# Power_PCB.net
KiCad netlist of a schematic drawn in EAGLE
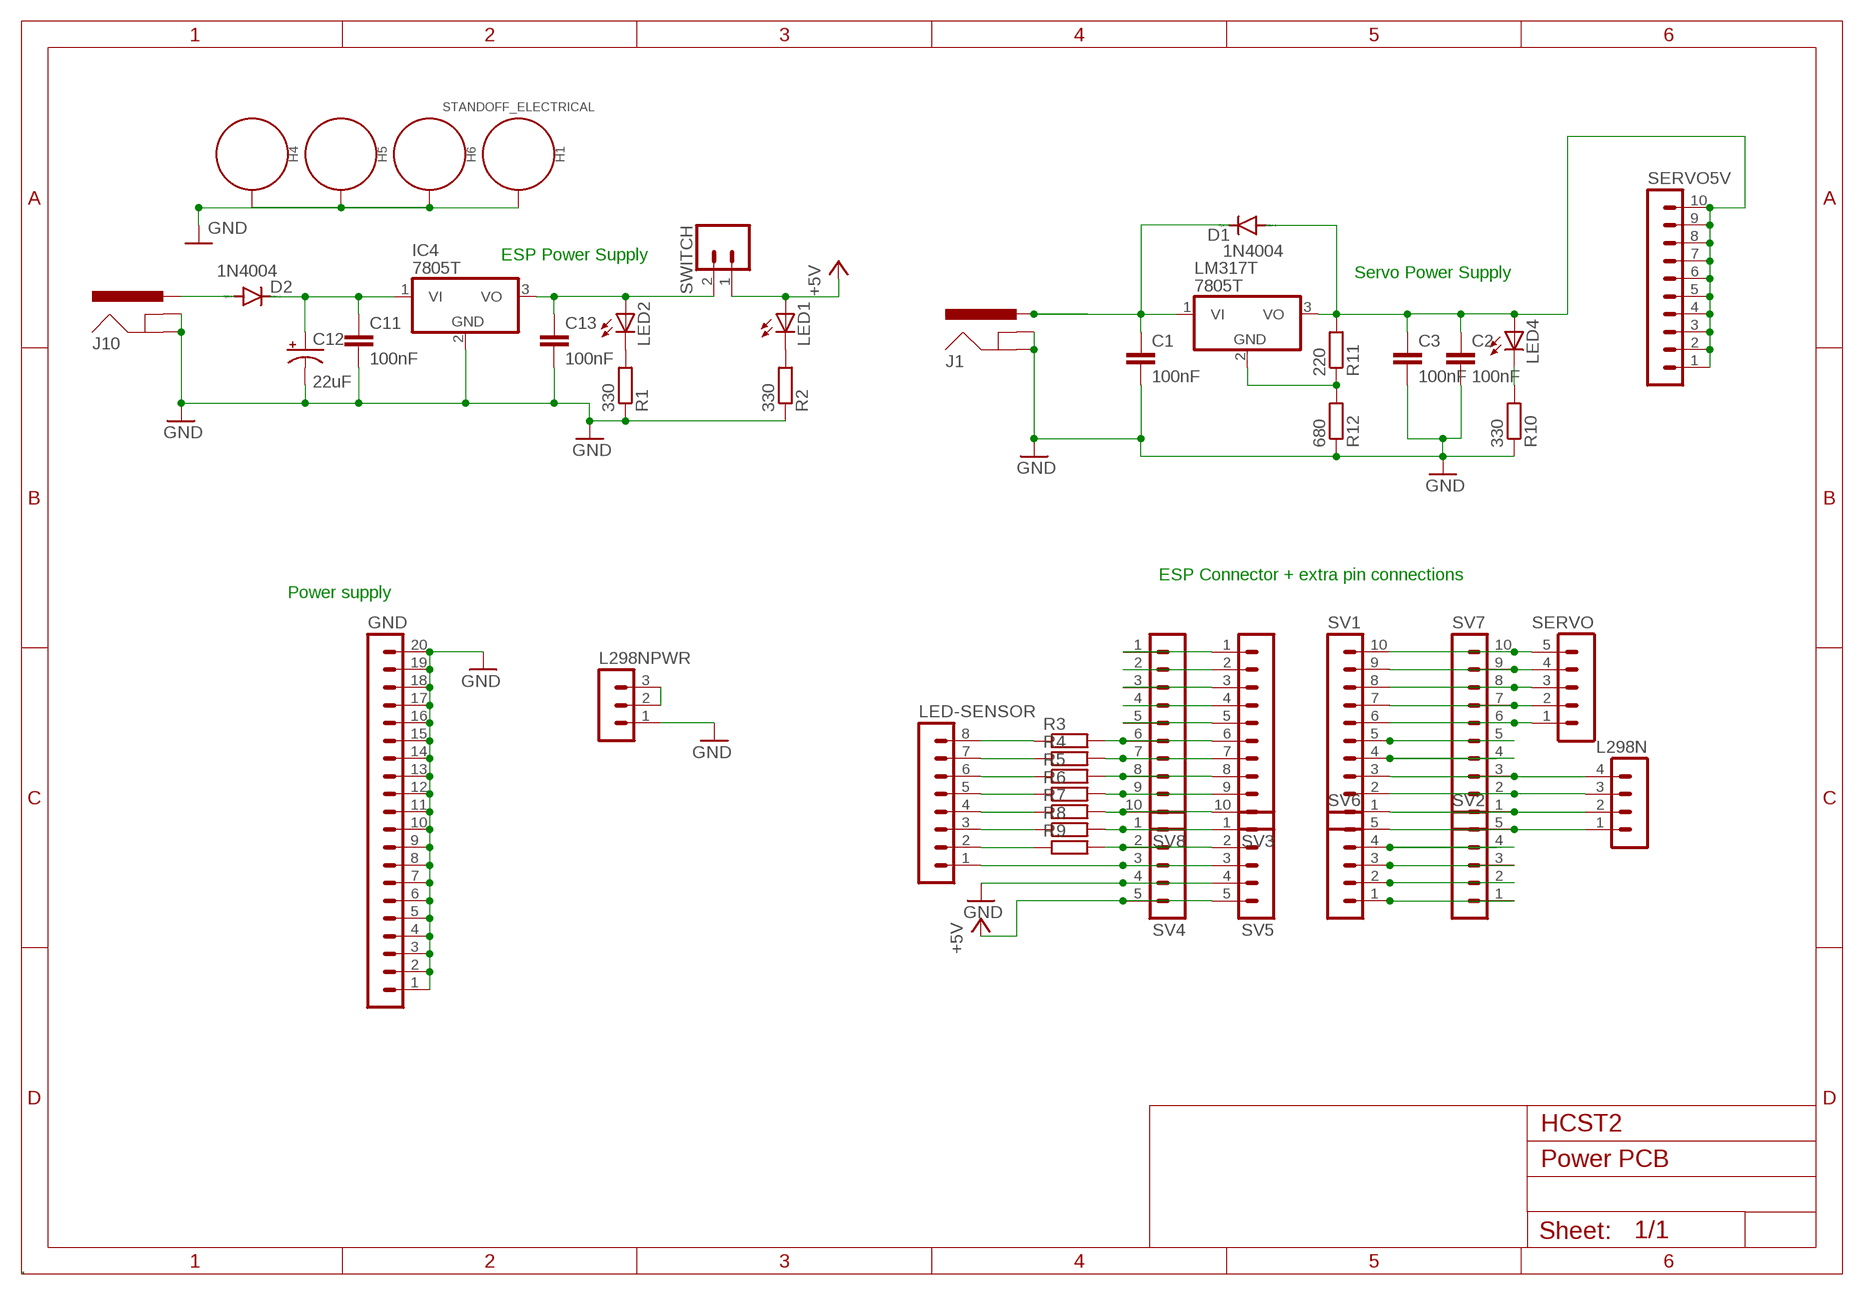
[diagram p0: schematic, sheet 1]

(export (version "E")
  (design (tool "Eeschema 10.0.6"))
  (components
    (comp (ref "C1")
      (value "100nF")
      (footprint "eagle-import:C2.5-2")
      (libsource (lib "eagle-import") (part "C2.5/2"))
    )
    (comp (ref "C2")
      (value "100nF")
      (footprint "eagle-import:C2.5-2")
      (libsource (lib "eagle-import") (part "C2.5/2"))
    )
    (comp (ref "C3")
      (value "100nF")
      (footprint "eagle-import:C2.5-2")
      (libsource (lib "eagle-import") (part "C2.5/2"))
    )
    (comp (ref "C11")
      (value "100nF")
      (footprint "eagle-import:C2.5-2")
      (libsource (lib "eagle-import") (part "C2.5/2"))
    )
    (comp (ref "C12")
      (value "22uF")
      (footprint "eagle-import:E2,5-7")
      (libsource (lib "eagle-import") (part "CPOL-USE2.5-7"))
    )
    (comp (ref "C13")
      (value "100nF")
      (footprint "eagle-import:C2.5-2")
      (libsource (lib "eagle-import") (part "C2.5/2"))
    )
    (comp (ref "D1")
      (value "1N4004")
      (footprint "eagle-import:DO41-10")
      (libsource (lib "eagle-import") (part "1N4004"))
    )
    (comp (ref "D2")
      (value "1N4004")
      (footprint "eagle-import:DO41-10")
      (libsource (lib "eagle-import") (part "1N4004"))
    )
    (comp (ref "GND")
      (value "MA20-1")
      (footprint "eagle-import:MA20-1")
      (libsource (lib "eagle-import") (part "MA20-1"))
    )
    (comp (ref "H1")
      (value "STANDOFF_ELECTRICAL")
      (footprint "eagle-import:STANDOFF-ELECTRICAL")
      (libsource (lib "eagle-import") (part "STANDOFF_ELECTRICAL"))
    )
    (comp (ref "H4")
      (value "STANDOFF_ELECTRICAL")
      (footprint "eagle-import:STANDOFF-ELECTRICAL")
      (libsource (lib "eagle-import") (part "SparkFun-Hardware_519_STANDOFF_ELECTRICAL"))
    )
    (comp (ref "H5")
      (value "STANDOFF_ELECTRICAL")
      (footprint "eagle-import:STANDOFF-ELECTRICAL")
      (libsource (lib "eagle-import") (part "SparkFun-Hardware_519_STANDOFF_ELECTRICAL"))
    )
    (comp (ref "H6")
      (value "STANDOFF_ELECTRICAL")
      (footprint "eagle-import:STANDOFF-ELECTRICAL")
      (libsource (lib "eagle-import") (part "SparkFun-Hardware_519_STANDOFF_ELECTRICAL"))
    )
    (comp (ref "IC4")
      (value "7805T")
      (footprint "eagle-import:TO220H")
      (libsource (lib "eagle-import") (part "78T05"))
    )
    (comp (ref "J1")
      (value "EL311-ROBOT_SPARKFUN-CONNECTORS_POWER_JACKPTH")
      (footprint "eagle-import:EL311-ROBOT_SPARKFUN-CONNECTORS_POWER_JACK_PTH")
      (libsource (lib "eagle-import") (part "EL311-ROBOT_SPARKFUN-CONNECTORS_POWER_JACKPTH"))
    )
    (comp (ref "J10")
      (value "EL311-ROBOT_SPARKFUN-CONNECTORS_POWER_JACKPTH")
      (footprint "eagle-import:EL311-ROBOT_SPARKFUN-CONNECTORS_POWER_JACK_PTH")
      (libsource (lib "eagle-import") (part "EL311-ROBOT_SPARKFUN-CONNECTORS_POWER_JACKPTH"))
    )
    (comp (ref "L298N")
      (value "MA04-1")
      (footprint "eagle-import:MA04-1")
      (libsource (lib "eagle-import") (part "MA04-1"))
    )
    (comp (ref "L298NPWR")
      (value "MA03-1")
      (footprint "eagle-import:MA03-1")
      (libsource (lib "eagle-import") (part "MA03-1"))
    )
    (comp (ref "LED-SENSOR")
      (value "MA08-1")
      (footprint "eagle-import:MA08-1")
      (libsource (lib "eagle-import") (part "MA08-1"))
    )
    (comp (ref "LED1")
      (value "LED3MM")
      (footprint "eagle-import:LED3MM")
      (libsource (lib "eagle-import") (part "LED3MM"))
    )
    (comp (ref "LED2")
      (value "LED3MM")
      (footprint "eagle-import:LED3MM")
      (libsource (lib "eagle-import") (part "LED3MM"))
    )
    (comp (ref "LED4")
      (value "LED3MM")
      (footprint "eagle-import:LED3MM")
      (libsource (lib "eagle-import") (part "LED3MM"))
    )
    (comp (ref "LM317T")
      (value "7805T")
      (footprint "eagle-import:TO220H")
      (libsource (lib "eagle-import") (part "78T05"))
    )
    (comp (ref "R1")
      (value "330")
      (footprint "eagle-import:0207_10")
      (libsource (lib "eagle-import") (part "R-EU_0207/10"))
    )
    (comp (ref "R2")
      (value "330")
      (footprint "eagle-import:0207_10")
      (libsource (lib "eagle-import") (part "R-EU_0207/10"))
    )
    (comp (ref "R3")
      (value "R-EU_0207/10")
      (footprint "eagle-import:0207_10")
      (libsource (lib "eagle-import") (part "R-EU_0207/10"))
    )
    (comp (ref "R4")
      (value "R-EU_0207/10")
      (footprint "eagle-import:0207_10")
      (libsource (lib "eagle-import") (part "R-EU_0207/10"))
    )
    (comp (ref "R5")
      (value "R-EU_0207/10")
      (footprint "eagle-import:0207_10")
      (libsource (lib "eagle-import") (part "R-EU_0207/10"))
    )
    (comp (ref "R6")
      (value "R-EU_0207/10")
      (footprint "eagle-import:0207_10")
      (libsource (lib "eagle-import") (part "R-EU_0207/10"))
    )
    (comp (ref "R7")
      (value "R-EU_0207/10")
      (footprint "eagle-import:0207_10")
      (libsource (lib "eagle-import") (part "R-EU_0207/10"))
    )
    (comp (ref "R8")
      (value "R-EU_0207/10")
      (footprint "eagle-import:0207_10")
      (libsource (lib "eagle-import") (part "R-EU_0207/10"))
    )
    (comp (ref "R9")
      (value "R-EU_0207/10")
      (footprint "eagle-import:0207_10")
      (libsource (lib "eagle-import") (part "R-EU_0207/10"))
    )
    (comp (ref "R10")
      (value "330")
      (footprint "eagle-import:0207_10")
      (libsource (lib "eagle-import") (part "R-EU_0207/10"))
    )
    (comp (ref "R11")
      (value "220")
      (footprint "eagle-import:0207_10")
      (libsource (lib "eagle-import") (part "R-EU_0207/10"))
    )
    (comp (ref "R12")
      (value "680")
      (footprint "eagle-import:0207_10")
      (libsource (lib "eagle-import") (part "R-EU_0207/10"))
    )
    (comp (ref "SERVO")
      (value "MA05-1")
      (footprint "eagle-import:MA05-1")
      (libsource (lib "eagle-import") (part "MA05-1"))
    )
    (comp (ref "SERVO5V")
      (value "MA10-1")
      (footprint "eagle-import:MA10-1")
      (libsource (lib "eagle-import") (part "MA10-1"))
    )
    (comp (ref "SV1")
      (value "MA10-1")
      (footprint "eagle-import:MA10-1")
      (libsource (lib "eagle-import") (part "MA10-1"))
    )
    (comp (ref "SV2")
      (value "MA05-1")
      (footprint "eagle-import:MA05-1")
      (libsource (lib "eagle-import") (part "MA05-1"))
    )
    (comp (ref "SV3")
      (value "MA10-1")
      (footprint "eagle-import:MA10-1")
      (libsource (lib "eagle-import") (part "MA10-1"))
    )
    (comp (ref "SV4")
      (value "MA05-1")
      (footprint "eagle-import:MA05-1")
      (libsource (lib "eagle-import") (part "MA05-1"))
    )
    (comp (ref "SV5")
      (value "MA05-1")
      (footprint "eagle-import:MA05-1")
      (libsource (lib "eagle-import") (part "MA05-1"))
    )
    (comp (ref "SV6")
      (value "MA05-1")
      (footprint "eagle-import:MA05-1")
      (libsource (lib "eagle-import") (part "MA05-1"))
    )
    (comp (ref "SV7")
      (value "MA10-1")
      (footprint "eagle-import:MA10-1")
      (libsource (lib "eagle-import") (part "MA10-1"))
    )
    (comp (ref "SV8")
      (value "MA10-1")
      (footprint "eagle-import:MA10-1")
      (libsource (lib "eagle-import") (part "MA10-1"))
    )
    (comp (ref "SWITCH")
      (value "CONN_02")
      (footprint "eagle-import:1X02")
      (libsource (lib "eagle-import") (part "CONN_02"))
    )
  )
  (nets
    (net (code "1") (name "+5V") (class "Default")
      (node (ref "LED1") (pin "A") (pinfunction "A_A") (pintype "passive"))
      (node (ref "SV4") (pin "5") (pinfunction "5_5") (pintype "passive"))
      (node (ref "SV5") (pin "5") (pinfunction "5_5") (pintype "passive"))
      (node (ref "SWITCH") (pin "1") (pinfunction "1_1") (pintype "passive"))
    )
    (net (code "2") (name "GND") (class "Default")
      (node (ref "C1") (pin "2") (pinfunction "2_2") (pintype "passive"))
      (node (ref "C11") (pin "2") (pinfunction "2_2") (pintype "passive"))
      (node (ref "C12") (pin "-") (pinfunction "-_-") (pintype "passive"))
      (node (ref "C13") (pin "2") (pinfunction "2_2") (pintype "passive"))
      (node (ref "C2") (pin "2") (pinfunction "2_2") (pintype "passive"))
      (node (ref "C3") (pin "2") (pinfunction "2_2") (pintype "passive"))
      (node (ref "GND") (pin "1") (pinfunction "1_1") (pintype "passive"))
      (node (ref "GND") (pin "10") (pinfunction "10_10") (pintype "passive"))
      (node (ref "GND") (pin "11") (pinfunction "11_11") (pintype "passive"))
      (node (ref "GND") (pin "12") (pinfunction "12_12") (pintype "passive"))
      (node (ref "GND") (pin "13") (pinfunction "13_13") (pintype "passive"))
      (node (ref "GND") (pin "14") (pinfunction "14_14") (pintype "passive"))
      (node (ref "GND") (pin "15") (pinfunction "15_15") (pintype "passive"))
      (node (ref "GND") (pin "16") (pinfunction "16_16") (pintype "passive"))
      (node (ref "GND") (pin "17") (pinfunction "17_17") (pintype "passive"))
      (node (ref "GND") (pin "18") (pinfunction "18_18") (pintype "passive"))
      (node (ref "GND") (pin "19") (pinfunction "19_19") (pintype "passive"))
      (node (ref "GND") (pin "2") (pinfunction "2_2") (pintype "passive"))
      (node (ref "GND") (pin "20") (pinfunction "20_20") (pintype "passive"))
      (node (ref "GND") (pin "3") (pinfunction "3_3") (pintype "passive"))
      (node (ref "GND") (pin "4") (pinfunction "4_4") (pintype "passive"))
      (node (ref "GND") (pin "5") (pinfunction "5_5") (pintype "passive"))
      (node (ref "GND") (pin "6") (pinfunction "6_6") (pintype "passive"))
      (node (ref "GND") (pin "7") (pinfunction "7_7") (pintype "passive"))
      (node (ref "GND") (pin "8") (pinfunction "8_8") (pintype "passive"))
      (node (ref "GND") (pin "9") (pinfunction "9_9") (pintype "passive"))
      (node (ref "H1") (pin "P1") (pinfunction "P$1_P1") (pintype "bidirectional"))
      (node (ref "H4") (pin "P1") (pinfunction "P$1_P1") (pintype "bidirectional"))
      (node (ref "H5") (pin "P1") (pinfunction "P$1_P1") (pintype "bidirectional"))
      (node (ref "H6") (pin "P1") (pinfunction "P$1_P1") (pintype "bidirectional"))
      (node (ref "IC4") (pin "2") (pinfunction "GND_2") (pintype "passive"))
      (node (ref "J1") (pin "GND") (pinfunction "GND_GND") (pintype "bidirectional"))
      (node (ref "J1") (pin "GNDBREAK") (pinfunction "GNDBREAK_GNDBREAK") (pintype "bidirectional"))
      (node (ref "J10") (pin "GND") (pinfunction "GND_GND") (pintype "bidirectional"))
      (node (ref "J10") (pin "GNDBREAK") (pinfunction "GNDBREAK_GNDBREAK") (pintype "bidirectional"))
      (node (ref "L298NPWR") (pin "1") (pinfunction "1_1") (pintype "passive"))
      (node (ref "R1") (pin "1") (pinfunction "1_1") (pintype "passive"))
      (node (ref "R10") (pin "1") (pinfunction "1_1") (pintype "passive"))
      (node (ref "R12") (pin "1") (pinfunction "1_1") (pintype "passive"))
      (node (ref "R2") (pin "1") (pinfunction "1_1") (pintype "passive"))
      (node (ref "SV4") (pin "4") (pinfunction "4_4") (pintype "passive"))
      (node (ref "SV5") (pin "4") (pinfunction "4_4") (pintype "passive"))
    )
    (net (code "3") (name "Net-(D2-PadA)") (class "Default")
      (node (ref "D2") (pin "A") (pinfunction "A_A") (pintype "passive"))
      (node (ref "J10") (pin "PWR") (pinfunction "PWR_PWR") (pintype "bidirectional"))
    )
    (net (code "4") (name "Net-(IC4-VI)") (class "Default")
      (node (ref "C11") (pin "1") (pinfunction "1_1") (pintype "passive"))
      (node (ref "C12") (pin "+") (pinfunction "+_+") (pintype "passive"))
      (node (ref "D2") (pin "C") (pinfunction "C_C") (pintype "passive"))
      (node (ref "IC4") (pin "1") (pinfunction "VI_1") (pintype "input"))
    )
    (net (code "5") (name "Net-(IC4-VO)") (class "Default")
      (node (ref "C13") (pin "1") (pinfunction "1_1") (pintype "passive"))
      (node (ref "IC4") (pin "3") (pinfunction "VO_3") (pintype "passive"))
      (node (ref "LED2") (pin "A") (pinfunction "A_A") (pintype "passive"))
      (node (ref "SWITCH") (pin "2") (pinfunction "2_2") (pintype "passive"))
    )
    (net (code "6") (name "Net-(L298N-Pad1)") (class "Default")
      (node (ref "L298N") (pin "1") (pinfunction "1_1") (pintype "passive"))
      (node (ref "SV2") (pin "5") (pinfunction "5_5") (pintype "passive"))
      (node (ref "SV6") (pin "5") (pinfunction "5_5") (pintype "passive"))
    )
    (net (code "7") (name "Net-(L298N-Pad2)") (class "Default")
      (node (ref "L298N") (pin "2") (pinfunction "2_2") (pintype "passive"))
      (node (ref "SV1") (pin "1") (pinfunction "1_1") (pintype "passive"))
      (node (ref "SV7") (pin "1") (pinfunction "1_1") (pintype "passive"))
    )
    (net (code "8") (name "Net-(L298N-Pad3)") (class "Default")
      (node (ref "L298N") (pin "3") (pinfunction "3_3") (pintype "passive"))
      (node (ref "SV1") (pin "2") (pinfunction "2_2") (pintype "passive"))
      (node (ref "SV7") (pin "2") (pinfunction "2_2") (pintype "passive"))
    )
    (net (code "9") (name "Net-(L298N-Pad4)") (class "Default")
      (node (ref "L298N") (pin "4") (pinfunction "4_4") (pintype "passive"))
      (node (ref "SV1") (pin "3") (pinfunction "3_3") (pintype "passive"))
      (node (ref "SV7") (pin "3") (pinfunction "3_3") (pintype "passive"))
    )
    (net (code "10") (name "Net-(L298NPWR-Pad2)") (class "Default")
      (node (ref "L298NPWR") (pin "2") (pinfunction "2_2") (pintype "passive"))
      (node (ref "L298NPWR") (pin "3") (pinfunction "3_3") (pintype "passive"))
    )
    (net (code "11") (name "Net-(LED-SENSOR-Pad1)") (class "Default")
      (node (ref "LED-SENSOR") (pin "1") (pinfunction "1_1") (pintype "passive"))
      (node (ref "SV4") (pin "3") (pinfunction "3_3") (pintype "passive"))
      (node (ref "SV5") (pin "3") (pinfunction "3_3") (pintype "passive"))
    )
    (net (code "12") (name "Net-(LED-SENSOR-Pad2)") (class "Default")
      (node (ref "LED-SENSOR") (pin "2") (pinfunction "2_2") (pintype "passive"))
      (node (ref "R9") (pin "1") (pinfunction "1_1") (pintype "passive"))
    )
    (net (code "13") (name "Net-(LED-SENSOR-Pad3)") (class "Default")
      (node (ref "LED-SENSOR") (pin "3") (pinfunction "3_3") (pintype "passive"))
      (node (ref "R8") (pin "1") (pinfunction "1_1") (pintype "passive"))
    )
    (net (code "14") (name "Net-(LED-SENSOR-Pad4)") (class "Default")
      (node (ref "LED-SENSOR") (pin "4") (pinfunction "4_4") (pintype "passive"))
      (node (ref "R7") (pin "1") (pinfunction "1_1") (pintype "passive"))
    )
    (net (code "15") (name "Net-(LED-SENSOR-Pad5)") (class "Default")
      (node (ref "LED-SENSOR") (pin "5") (pinfunction "5_5") (pintype "passive"))
      (node (ref "R6") (pin "1") (pinfunction "1_1") (pintype "passive"))
    )
    (net (code "16") (name "Net-(LED-SENSOR-Pad6)") (class "Default")
      (node (ref "LED-SENSOR") (pin "6") (pinfunction "6_6") (pintype "passive"))
      (node (ref "R5") (pin "1") (pinfunction "1_1") (pintype "passive"))
    )
    (net (code "17") (name "Net-(LED-SENSOR-Pad7)") (class "Default")
      (node (ref "LED-SENSOR") (pin "7") (pinfunction "7_7") (pintype "passive"))
      (node (ref "R4") (pin "1") (pinfunction "1_1") (pintype "passive"))
    )
    (net (code "18") (name "Net-(LED-SENSOR-Pad8)") (class "Default")
      (node (ref "LED-SENSOR") (pin "8") (pinfunction "8_8") (pintype "passive"))
      (node (ref "R3") (pin "1") (pinfunction "1_1") (pintype "passive"))
    )
    (net (code "19") (name "Net-(LED1-C)") (class "Default")
      (node (ref "LED1") (pin "K") (pinfunction "C_K") (pintype "passive"))
      (node (ref "R2") (pin "2") (pinfunction "2_2") (pintype "passive"))
    )
    (net (code "20") (name "Net-(LED2-C)") (class "Default")
      (node (ref "LED2") (pin "K") (pinfunction "C_K") (pintype "passive"))
      (node (ref "R1") (pin "2") (pinfunction "2_2") (pintype "passive"))
    )
    (net (code "21") (name "Net-(LED4-C)") (class "Default")
      (node (ref "LED4") (pin "K") (pinfunction "C_K") (pintype "passive"))
      (node (ref "R10") (pin "2") (pinfunction "2_2") (pintype "passive"))
    )
    (net (code "22") (name "Net-(LM317T-GND)") (class "Default")
      (node (ref "LM317T") (pin "2") (pinfunction "GND_2") (pintype "passive"))
      (node (ref "R11") (pin "1") (pinfunction "1_1") (pintype "passive"))
      (node (ref "R12") (pin "2") (pinfunction "2_2") (pintype "passive"))
    )
    (net (code "23") (name "Net-(LM317T-VI)") (class "Default")
      (node (ref "C1") (pin "1") (pinfunction "1_1") (pintype "passive"))
      (node (ref "D1") (pin "C") (pinfunction "C_C") (pintype "passive"))
      (node (ref "J1") (pin "PWR") (pinfunction "PWR_PWR") (pintype "bidirectional"))
      (node (ref "LM317T") (pin "1") (pinfunction "VI_1") (pintype "input"))
    )
    (net (code "24") (name "Net-(LM317T-VO)") (class "Default")
      (node (ref "C2") (pin "1") (pinfunction "1_1") (pintype "passive"))
      (node (ref "C3") (pin "1") (pinfunction "1_1") (pintype "passive"))
      (node (ref "D1") (pin "A") (pinfunction "A_A") (pintype "passive"))
      (node (ref "LED4") (pin "A") (pinfunction "A_A") (pintype "passive"))
      (node (ref "LM317T") (pin "3") (pinfunction "VO_3") (pintype "passive"))
      (node (ref "R11") (pin "2") (pinfunction "2_2") (pintype "passive"))
      (node (ref "SERVO5V") (pin "1") (pinfunction "1_1") (pintype "passive"))
      (node (ref "SERVO5V") (pin "10") (pinfunction "10_10") (pintype "passive"))
      (node (ref "SERVO5V") (pin "2") (pinfunction "2_2") (pintype "passive"))
      (node (ref "SERVO5V") (pin "3") (pinfunction "3_3") (pintype "passive"))
      (node (ref "SERVO5V") (pin "4") (pinfunction "4_4") (pintype "passive"))
      (node (ref "SERVO5V") (pin "5") (pinfunction "5_5") (pintype "passive"))
      (node (ref "SERVO5V") (pin "6") (pinfunction "6_6") (pintype "passive"))
      (node (ref "SERVO5V") (pin "7") (pinfunction "7_7") (pintype "passive"))
      (node (ref "SERVO5V") (pin "8") (pinfunction "8_8") (pintype "passive"))
      (node (ref "SERVO5V") (pin "9") (pinfunction "9_9") (pintype "passive"))
    )
    (net (code "25") (name "Net-(R3-Pad2)") (class "Default")
      (node (ref "R3") (pin "2") (pinfunction "2_2") (pintype "passive"))
      (node (ref "SV3") (pin "6") (pinfunction "6_6") (pintype "passive"))
      (node (ref "SV8") (pin "6") (pinfunction "6_6") (pintype "passive"))
    )
    (net (code "26") (name "Net-(R4-Pad2)") (class "Default")
      (node (ref "R4") (pin "2") (pinfunction "2_2") (pintype "passive"))
      (node (ref "SV3") (pin "7") (pinfunction "7_7") (pintype "passive"))
      (node (ref "SV8") (pin "7") (pinfunction "7_7") (pintype "passive"))
    )
    (net (code "27") (name "Net-(R5-Pad2)") (class "Default")
      (node (ref "R5") (pin "2") (pinfunction "2_2") (pintype "passive"))
      (node (ref "SV3") (pin "8") (pinfunction "8_8") (pintype "passive"))
      (node (ref "SV8") (pin "8") (pinfunction "8_8") (pintype "passive"))
    )
    (net (code "28") (name "Net-(R6-Pad2)") (class "Default")
      (node (ref "R6") (pin "2") (pinfunction "2_2") (pintype "passive"))
      (node (ref "SV3") (pin "9") (pinfunction "9_9") (pintype "passive"))
      (node (ref "SV8") (pin "9") (pinfunction "9_9") (pintype "passive"))
    )
    (net (code "29") (name "Net-(R7-Pad2)") (class "Default")
      (node (ref "R7") (pin "2") (pinfunction "2_2") (pintype "passive"))
      (node (ref "SV3") (pin "10") (pinfunction "10_10") (pintype "passive"))
      (node (ref "SV8") (pin "10") (pinfunction "10_10") (pintype "passive"))
    )
    (net (code "30") (name "Net-(R8-Pad2)") (class "Default")
      (node (ref "R8") (pin "2") (pinfunction "2_2") (pintype "passive"))
      (node (ref "SV4") (pin "1") (pinfunction "1_1") (pintype "passive"))
      (node (ref "SV5") (pin "1") (pinfunction "1_1") (pintype "passive"))
    )
    (net (code "31") (name "Net-(R9-Pad2)") (class "Default")
      (node (ref "R9") (pin "2") (pinfunction "2_2") (pintype "passive"))
      (node (ref "SV4") (pin "2") (pinfunction "2_2") (pintype "passive"))
      (node (ref "SV5") (pin "2") (pinfunction "2_2") (pintype "passive"))
    )
    (net (code "32") (name "Net-(SERVO-Pad1)") (class "Default")
      (node (ref "SERVO") (pin "1") (pinfunction "1_1") (pintype "passive"))
      (node (ref "SV1") (pin "6") (pinfunction "6_6") (pintype "passive"))
      (node (ref "SV7") (pin "6") (pinfunction "6_6") (pintype "passive"))
    )
    (net (code "33") (name "Net-(SERVO-Pad2)") (class "Default")
      (node (ref "SERVO") (pin "2") (pinfunction "2_2") (pintype "passive"))
      (node (ref "SV1") (pin "7") (pinfunction "7_7") (pintype "passive"))
      (node (ref "SV7") (pin "7") (pinfunction "7_7") (pintype "passive"))
    )
    (net (code "34") (name "Net-(SERVO-Pad3)") (class "Default")
      (node (ref "SERVO") (pin "3") (pinfunction "3_3") (pintype "passive"))
      (node (ref "SV1") (pin "8") (pinfunction "8_8") (pintype "passive"))
      (node (ref "SV7") (pin "8") (pinfunction "8_8") (pintype "passive"))
    )
    (net (code "35") (name "Net-(SERVO-Pad4)") (class "Default")
      (node (ref "SERVO") (pin "4") (pinfunction "4_4") (pintype "passive"))
      (node (ref "SV1") (pin "9") (pinfunction "9_9") (pintype "passive"))
      (node (ref "SV7") (pin "9") (pinfunction "9_9") (pintype "passive"))
    )
    (net (code "36") (name "Net-(SERVO-Pad5)") (class "Default")
      (node (ref "SERVO") (pin "5") (pinfunction "5_5") (pintype "passive"))
      (node (ref "SV1") (pin "10") (pinfunction "10_10") (pintype "passive"))
      (node (ref "SV7") (pin "10") (pinfunction "10_10") (pintype "passive"))
    )
    (net (code "37") (name "Net-(SV1-Pad4)") (class "Default")
      (node (ref "SV1") (pin "4") (pinfunction "4_4") (pintype "passive"))
      (node (ref "SV7") (pin "4") (pinfunction "4_4") (pintype "passive"))
    )
    (net (code "38") (name "Net-(SV1-Pad5)") (class "Default")
      (node (ref "SV1") (pin "5") (pinfunction "5_5") (pintype "passive"))
      (node (ref "SV7") (pin "5") (pinfunction "5_5") (pintype "passive"))
    )
    (net (code "39") (name "Net-(SV2-Pad1)") (class "Default")
      (node (ref "SV2") (pin "1") (pinfunction "1_1") (pintype "passive"))
      (node (ref "SV6") (pin "1") (pinfunction "1_1") (pintype "passive"))
    )
    (net (code "40") (name "Net-(SV2-Pad2)") (class "Default")
      (node (ref "SV2") (pin "2") (pinfunction "2_2") (pintype "passive"))
      (node (ref "SV6") (pin "2") (pinfunction "2_2") (pintype "passive"))
    )
    (net (code "41") (name "Net-(SV2-Pad3)") (class "Default")
      (node (ref "SV2") (pin "3") (pinfunction "3_3") (pintype "passive"))
      (node (ref "SV6") (pin "3") (pinfunction "3_3") (pintype "passive"))
    )
    (net (code "42") (name "Net-(SV2-Pad4)") (class "Default")
      (node (ref "SV2") (pin "4") (pinfunction "4_4") (pintype "passive"))
      (node (ref "SV6") (pin "4") (pinfunction "4_4") (pintype "passive"))
    )
    (net (code "43") (name "Net-(SV3-Pad1)") (class "Default")
      (node (ref "SV3") (pin "1") (pinfunction "1_1") (pintype "passive"))
      (node (ref "SV8") (pin "1") (pinfunction "1_1") (pintype "passive"))
    )
    (net (code "44") (name "Net-(SV3-Pad2)") (class "Default")
      (node (ref "SV3") (pin "2") (pinfunction "2_2") (pintype "passive"))
      (node (ref "SV8") (pin "2") (pinfunction "2_2") (pintype "passive"))
    )
    (net (code "45") (name "Net-(SV3-Pad3)") (class "Default")
      (node (ref "SV3") (pin "3") (pinfunction "3_3") (pintype "passive"))
      (node (ref "SV8") (pin "3") (pinfunction "3_3") (pintype "passive"))
    )
    (net (code "46") (name "Net-(SV3-Pad4)") (class "Default")
      (node (ref "SV3") (pin "4") (pinfunction "4_4") (pintype "passive"))
      (node (ref "SV8") (pin "4") (pinfunction "4_4") (pintype "passive"))
    )
    (net (code "47") (name "Net-(SV3-Pad5)") (class "Default")
      (node (ref "SV3") (pin "5") (pinfunction "5_5") (pintype "passive"))
      (node (ref "SV8") (pin "5") (pinfunction "5_5") (pintype "passive"))
    )
  )
)
